# PixelBar-w6Pixels.net
KiCad netlist of a schematic drawn in EAGLE
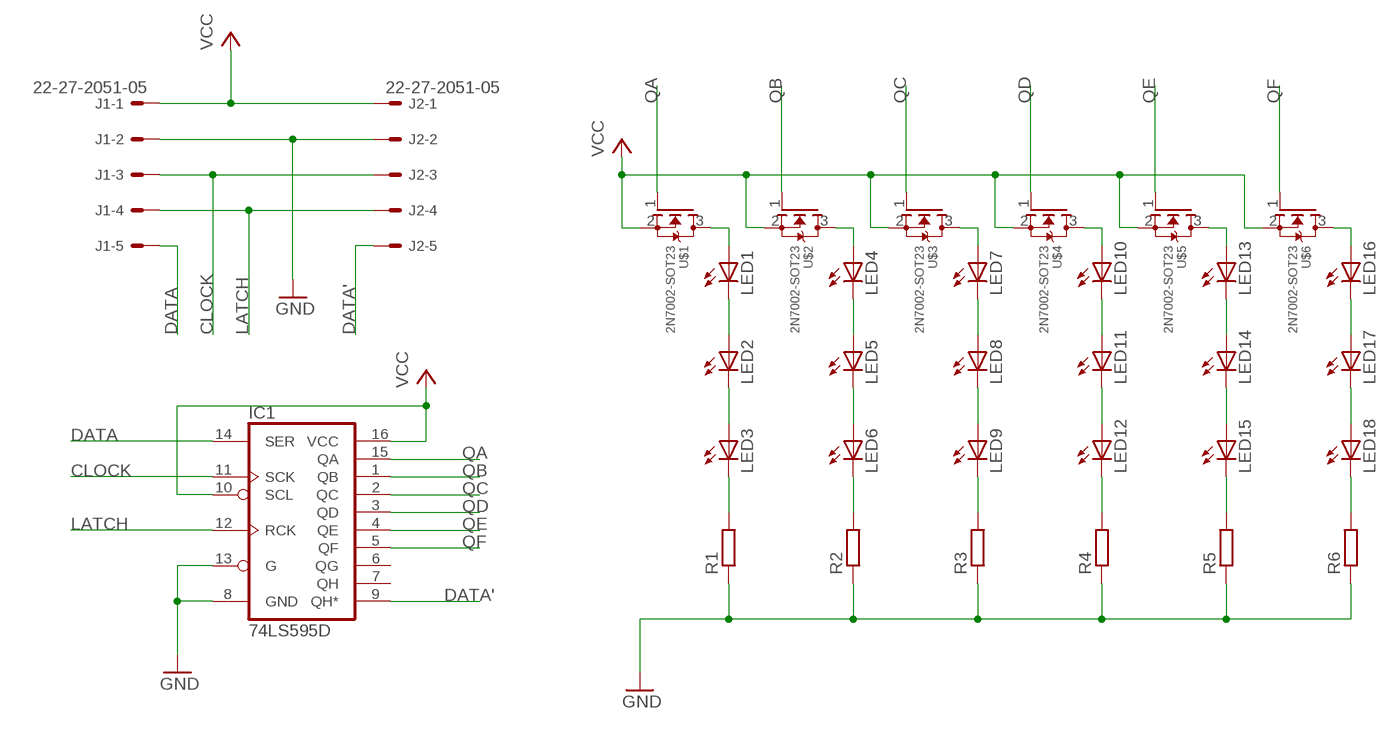
[diagram p0: schematic, sheet 1]

(export (version "E")
  (design (tool "Eeschema 10.0.6"))
  (components
    (comp (ref "IC1")
      (value "74LS595D")
      (footprint "eagle-import:SO16")
      (libsource (lib "eagle-import") (part "74595DLS"))
    )
    (comp (ref "J1")
      (value "22-27-2051-05")
      (footprint "eagle-import:6410-05")
      (libsource (lib "eagle-import") (part "22-?-0527-2051"))
    )
    (comp (ref "J2")
      (value "22-27-2051-05")
      (footprint "eagle-import:6410-05")
      (libsource (lib "eagle-import") (part "22-?-0527-2051"))
    )
    (comp (ref "LED1")
      (value "LED5MM")
      (footprint "eagle-import:LED5MM")
      (libsource (lib "eagle-import") (part "LED5MM"))
    )
    (comp (ref "LED2")
      (value "LED5MM")
      (footprint "eagle-import:LED5MM")
      (libsource (lib "eagle-import") (part "LED5MM"))
    )
    (comp (ref "LED3")
      (value "LED5MM")
      (footprint "eagle-import:LED5MM")
      (libsource (lib "eagle-import") (part "LED5MM"))
    )
    (comp (ref "LED4")
      (value "LED5MM")
      (footprint "eagle-import:LED5MM")
      (libsource (lib "eagle-import") (part "LED5MM"))
    )
    (comp (ref "LED5")
      (value "LED5MM")
      (footprint "eagle-import:LED5MM")
      (libsource (lib "eagle-import") (part "LED5MM"))
    )
    (comp (ref "LED6")
      (value "LED5MM")
      (footprint "eagle-import:LED5MM")
      (libsource (lib "eagle-import") (part "LED5MM"))
    )
    (comp (ref "LED7")
      (value "LED5MM")
      (footprint "eagle-import:LED5MM")
      (libsource (lib "eagle-import") (part "LED5MM"))
    )
    (comp (ref "LED8")
      (value "LED5MM")
      (footprint "eagle-import:LED5MM")
      (libsource (lib "eagle-import") (part "LED5MM"))
    )
    (comp (ref "LED9")
      (value "LED5MM")
      (footprint "eagle-import:LED5MM")
      (libsource (lib "eagle-import") (part "LED5MM"))
    )
    (comp (ref "LED10")
      (value "LED5MM")
      (footprint "eagle-import:LED5MM")
      (libsource (lib "eagle-import") (part "LED5MM"))
    )
    (comp (ref "LED11")
      (value "LED5MM")
      (footprint "eagle-import:LED5MM")
      (libsource (lib "eagle-import") (part "LED5MM"))
    )
    (comp (ref "LED12")
      (value "LED5MM")
      (footprint "eagle-import:LED5MM")
      (libsource (lib "eagle-import") (part "LED5MM"))
    )
    (comp (ref "LED13")
      (value "LED5MM")
      (footprint "eagle-import:LED5MM")
      (libsource (lib "eagle-import") (part "LED5MM"))
    )
    (comp (ref "LED14")
      (value "LED5MM")
      (footprint "eagle-import:LED5MM")
      (libsource (lib "eagle-import") (part "LED5MM"))
    )
    (comp (ref "LED15")
      (value "LED5MM")
      (footprint "eagle-import:LED5MM")
      (libsource (lib "eagle-import") (part "LED5MM"))
    )
    (comp (ref "LED16")
      (value "LED5MM")
      (footprint "eagle-import:LED5MM")
      (libsource (lib "eagle-import") (part "LED5MM"))
    )
    (comp (ref "LED17")
      (value "LED5MM")
      (footprint "eagle-import:LED5MM")
      (libsource (lib "eagle-import") (part "LED5MM"))
    )
    (comp (ref "LED18")
      (value "LED5MM")
      (footprint "eagle-import:LED5MM")
      (libsource (lib "eagle-import") (part "LED5MM"))
    )
    (comp (ref "R1")
      (value "RESISTOR-1/4W-SMD-1206")
      (footprint "eagle-import:R1206")
      (libsource (lib "eagle-import") (part "RESISTOR-1/4W-SMD-1206"))
    )
    (comp (ref "R2")
      (value "RESISTOR-1/4W-SMD-1206")
      (footprint "eagle-import:R1206")
      (libsource (lib "eagle-import") (part "RESISTOR-1/4W-SMD-1206"))
    )
    (comp (ref "R3")
      (value "RESISTOR-1/4W-SMD-1206")
      (footprint "eagle-import:R1206")
      (libsource (lib "eagle-import") (part "RESISTOR-1/4W-SMD-1206"))
    )
    (comp (ref "R4")
      (value "RESISTOR-1/4W-SMD-1206")
      (footprint "eagle-import:R1206")
      (libsource (lib "eagle-import") (part "RESISTOR-1/4W-SMD-1206"))
    )
    (comp (ref "R5")
      (value "RESISTOR-1/4W-SMD-1206")
      (footprint "eagle-import:R1206")
      (libsource (lib "eagle-import") (part "RESISTOR-1/4W-SMD-1206"))
    )
    (comp (ref "R6")
      (value "RESISTOR-1/4W-SMD-1206")
      (footprint "eagle-import:R1206")
      (libsource (lib "eagle-import") (part "RESISTOR-1/4W-SMD-1206"))
    )
    (comp (ref "U$1")
      (value "2N7002-SOT23")
      (footprint "eagle-import:SOT23")
      (libsource (lib "eagle-import") (part "2N7002-SOT23"))
    )
    (comp (ref "U$2")
      (value "2N7002-SOT23")
      (footprint "eagle-import:SOT23")
      (libsource (lib "eagle-import") (part "2N7002-SOT23"))
    )
    (comp (ref "U$3")
      (value "2N7002-SOT23")
      (footprint "eagle-import:SOT23")
      (libsource (lib "eagle-import") (part "2N7002-SOT23"))
    )
    (comp (ref "U$4")
      (value "2N7002-SOT23")
      (footprint "eagle-import:SOT23")
      (libsource (lib "eagle-import") (part "2N7002-SOT23"))
    )
    (comp (ref "U$5")
      (value "2N7002-SOT23")
      (footprint "eagle-import:SOT23")
      (libsource (lib "eagle-import") (part "2N7002-SOT23"))
    )
    (comp (ref "U$6")
      (value "2N7002-SOT23")
      (footprint "eagle-import:SOT23")
      (libsource (lib "eagle-import") (part "2N7002-SOT23"))
    )
  )
  (nets
    (net (code "1") (name "/CLOCK") (class "Default")
      (node (ref "IC1") (pin "11") (pinfunction "SCK_11") (pintype "input"))
      (node (ref "J1") (pin "3") (pinfunction "S_3") (pintype "passive"))
      (node (ref "J2") (pin "3") (pinfunction "S_3") (pintype "passive"))
    )
    (net (code "2") (name "/DATA") (class "Default")
      (node (ref "IC1") (pin "14") (pinfunction "SER_14") (pintype "input"))
      (node (ref "J1") (pin "5") (pinfunction "S_5") (pintype "passive"))
    )
    (net (code "3") (name "/DATA'") (class "Default")
      (node (ref "IC1") (pin "9") (pinfunction "QH*_9") (pintype "tri_state"))
      (node (ref "J2") (pin "5") (pinfunction "S_5") (pintype "passive"))
    )
    (net (code "4") (name "/LATCH") (class "Default")
      (node (ref "IC1") (pin "12") (pinfunction "RCK_12") (pintype "input"))
      (node (ref "J1") (pin "4") (pinfunction "S_4") (pintype "passive"))
      (node (ref "J2") (pin "4") (pinfunction "S_4") (pintype "passive"))
    )
    (net (code "5") (name "/QA") (class "Default")
      (node (ref "IC1") (pin "15") (pinfunction "QA_15") (pintype "tri_state"))
      (node (ref "U$1") (pin "1") (pinfunction "G_1") (pintype "passive"))
    )
    (net (code "6") (name "/QB") (class "Default")
      (node (ref "IC1") (pin "1") (pinfunction "QB_1") (pintype "tri_state"))
      (node (ref "U$2") (pin "1") (pinfunction "G_1") (pintype "passive"))
    )
    (net (code "7") (name "/QC") (class "Default")
      (node (ref "IC1") (pin "2") (pinfunction "QC_2") (pintype "tri_state"))
      (node (ref "U$3") (pin "1") (pinfunction "G_1") (pintype "passive"))
    )
    (net (code "8") (name "/QD") (class "Default")
      (node (ref "IC1") (pin "3") (pinfunction "QD_3") (pintype "tri_state"))
      (node (ref "U$4") (pin "1") (pinfunction "G_1") (pintype "passive"))
    )
    (net (code "9") (name "/QE") (class "Default")
      (node (ref "IC1") (pin "4") (pinfunction "QE_4") (pintype "tri_state"))
      (node (ref "U$5") (pin "1") (pinfunction "G_1") (pintype "passive"))
    )
    (net (code "10") (name "/QF") (class "Default")
      (node (ref "IC1") (pin "5") (pinfunction "QF_5") (pintype "tri_state"))
      (node (ref "U$6") (pin "1") (pinfunction "G_1") (pintype "passive"))
    )
    (net (code "11") (name "GND") (class "Default")
      (node (ref "IC1") (pin "13") (pinfunction "G_13") (pintype "input"))
      (node (ref "IC1") (pin "8") (pinfunction "GND_8") (pintype "power_in"))
      (node (ref "J1") (pin "2") (pinfunction "S_2") (pintype "passive"))
      (node (ref "J2") (pin "2") (pinfunction "S_2") (pintype "passive"))
      (node (ref "R1") (pin "P$1") (pinfunction "1_P$1") (pintype "passive"))
      (node (ref "R2") (pin "P$1") (pinfunction "1_P$1") (pintype "passive"))
      (node (ref "R3") (pin "P$1") (pinfunction "1_P$1") (pintype "passive"))
      (node (ref "R4") (pin "P$1") (pinfunction "1_P$1") (pintype "passive"))
      (node (ref "R5") (pin "P$1") (pinfunction "1_P$1") (pintype "passive"))
      (node (ref "R6") (pin "P$1") (pinfunction "1_P$1") (pintype "passive"))
    )
    (net (code "12") (name "Net-(LED1-C)") (class "Default")
      (node (ref "LED1") (pin "K") (pinfunction "C_K") (pintype "passive"))
      (node (ref "LED2") (pin "A") (pinfunction "A_A") (pintype "passive"))
    )
    (net (code "13") (name "Net-(LED2-C)") (class "Default")
      (node (ref "LED2") (pin "K") (pinfunction "C_K") (pintype "passive"))
      (node (ref "LED3") (pin "A") (pinfunction "A_A") (pintype "passive"))
    )
    (net (code "14") (name "Net-(LED3-C)") (class "Default")
      (node (ref "LED3") (pin "K") (pinfunction "C_K") (pintype "passive"))
      (node (ref "R1") (pin "P$2") (pinfunction "2_P$2") (pintype "passive"))
    )
    (net (code "15") (name "Net-(LED4-C)") (class "Default")
      (node (ref "LED4") (pin "K") (pinfunction "C_K") (pintype "passive"))
      (node (ref "LED5") (pin "A") (pinfunction "A_A") (pintype "passive"))
    )
    (net (code "16") (name "Net-(LED5-C)") (class "Default")
      (node (ref "LED5") (pin "K") (pinfunction "C_K") (pintype "passive"))
      (node (ref "LED6") (pin "A") (pinfunction "A_A") (pintype "passive"))
    )
    (net (code "17") (name "Net-(LED6-C)") (class "Default")
      (node (ref "LED6") (pin "K") (pinfunction "C_K") (pintype "passive"))
      (node (ref "R2") (pin "P$2") (pinfunction "2_P$2") (pintype "passive"))
    )
    (net (code "18") (name "Net-(LED7-C)") (class "Default")
      (node (ref "LED7") (pin "K") (pinfunction "C_K") (pintype "passive"))
      (node (ref "LED8") (pin "A") (pinfunction "A_A") (pintype "passive"))
    )
    (net (code "19") (name "Net-(LED8-C)") (class "Default")
      (node (ref "LED8") (pin "K") (pinfunction "C_K") (pintype "passive"))
      (node (ref "LED9") (pin "A") (pinfunction "A_A") (pintype "passive"))
    )
    (net (code "20") (name "Net-(LED9-C)") (class "Default")
      (node (ref "LED9") (pin "K") (pinfunction "C_K") (pintype "passive"))
      (node (ref "R3") (pin "P$2") (pinfunction "2_P$2") (pintype "passive"))
    )
    (net (code "21") (name "Net-(LED10-C)") (class "Default")
      (node (ref "LED10") (pin "K") (pinfunction "C_K") (pintype "passive"))
      (node (ref "LED11") (pin "A") (pinfunction "A_A") (pintype "passive"))
    )
    (net (code "22") (name "Net-(LED11-C)") (class "Default")
      (node (ref "LED11") (pin "K") (pinfunction "C_K") (pintype "passive"))
      (node (ref "LED12") (pin "A") (pinfunction "A_A") (pintype "passive"))
    )
    (net (code "23") (name "Net-(LED12-C)") (class "Default")
      (node (ref "LED12") (pin "K") (pinfunction "C_K") (pintype "passive"))
      (node (ref "R4") (pin "P$2") (pinfunction "2_P$2") (pintype "passive"))
    )
    (net (code "24") (name "Net-(LED13-C)") (class "Default")
      (node (ref "LED13") (pin "K") (pinfunction "C_K") (pintype "passive"))
      (node (ref "LED14") (pin "A") (pinfunction "A_A") (pintype "passive"))
    )
    (net (code "25") (name "Net-(LED14-C)") (class "Default")
      (node (ref "LED14") (pin "K") (pinfunction "C_K") (pintype "passive"))
      (node (ref "LED15") (pin "A") (pinfunction "A_A") (pintype "passive"))
    )
    (net (code "26") (name "Net-(LED15-C)") (class "Default")
      (node (ref "LED15") (pin "K") (pinfunction "C_K") (pintype "passive"))
      (node (ref "R5") (pin "P$2") (pinfunction "2_P$2") (pintype "passive"))
    )
    (net (code "27") (name "Net-(LED16-C)") (class "Default")
      (node (ref "LED16") (pin "K") (pinfunction "C_K") (pintype "passive"))
      (node (ref "LED17") (pin "A") (pinfunction "A_A") (pintype "passive"))
    )
    (net (code "28") (name "Net-(LED17-C)") (class "Default")
      (node (ref "LED17") (pin "K") (pinfunction "C_K") (pintype "passive"))
      (node (ref "LED18") (pin "A") (pinfunction "A_A") (pintype "passive"))
    )
    (net (code "29") (name "Net-(LED18-C)") (class "Default")
      (node (ref "LED18") (pin "K") (pinfunction "C_K") (pintype "passive"))
      (node (ref "R6") (pin "P$2") (pinfunction "2_P$2") (pintype "passive"))
    )
    (net (code "30") (name "Net-(U$1-D)") (class "Default")
      (node (ref "LED1") (pin "A") (pinfunction "A_A") (pintype "passive"))
      (node (ref "U$1") (pin "3") (pinfunction "D_3") (pintype "passive"))
    )
    (net (code "31") (name "Net-(U$2-D)") (class "Default")
      (node (ref "LED4") (pin "A") (pinfunction "A_A") (pintype "passive"))
      (node (ref "U$2") (pin "3") (pinfunction "D_3") (pintype "passive"))
    )
    (net (code "32") (name "Net-(U$3-D)") (class "Default")
      (node (ref "LED7") (pin "A") (pinfunction "A_A") (pintype "passive"))
      (node (ref "U$3") (pin "3") (pinfunction "D_3") (pintype "passive"))
    )
    (net (code "33") (name "Net-(U$4-D)") (class "Default")
      (node (ref "LED10") (pin "A") (pinfunction "A_A") (pintype "passive"))
      (node (ref "U$4") (pin "3") (pinfunction "D_3") (pintype "passive"))
    )
    (net (code "34") (name "Net-(U$5-D)") (class "Default")
      (node (ref "LED13") (pin "A") (pinfunction "A_A") (pintype "passive"))
      (node (ref "U$5") (pin "3") (pinfunction "D_3") (pintype "passive"))
    )
    (net (code "35") (name "Net-(U$6-D)") (class "Default")
      (node (ref "LED16") (pin "A") (pinfunction "A_A") (pintype "passive"))
      (node (ref "U$6") (pin "3") (pinfunction "D_3") (pintype "passive"))
    )
    (net (code "36") (name "VCC") (class "Default")
      (node (ref "IC1") (pin "10") (pinfunction "SCL_10") (pintype "input"))
      (node (ref "IC1") (pin "16") (pinfunction "VCC_16") (pintype "power_in"))
      (node (ref "J1") (pin "1") (pinfunction "S_1") (pintype "passive"))
      (node (ref "J2") (pin "1") (pinfunction "S_1") (pintype "passive"))
      (node (ref "U$1") (pin "2") (pinfunction "S_2") (pintype "passive"))
      (node (ref "U$2") (pin "2") (pinfunction "S_2") (pintype "passive"))
      (node (ref "U$3") (pin "2") (pinfunction "S_2") (pintype "passive"))
      (node (ref "U$4") (pin "2") (pinfunction "S_2") (pintype "passive"))
      (node (ref "U$5") (pin "2") (pinfunction "S_2") (pintype "passive"))
      (node (ref "U$6") (pin "2") (pinfunction "S_2") (pintype "passive"))
    )
    (net (code "37") (name "unconnected-(IC1-QG-Pad6)") (class "Default")
      (node (ref "IC1") (pin "6") (pinfunction "QG_6") (pintype "tri_state"))
    )
    (net (code "38") (name "unconnected-(IC1-QH-Pad7)") (class "Default")
      (node (ref "IC1") (pin "7") (pinfunction "QH_7") (pintype "tri_state"))
    )
  )
)
